# DigitalClock-7221.net
KiCad netlist of a schematic drawn in EAGLE
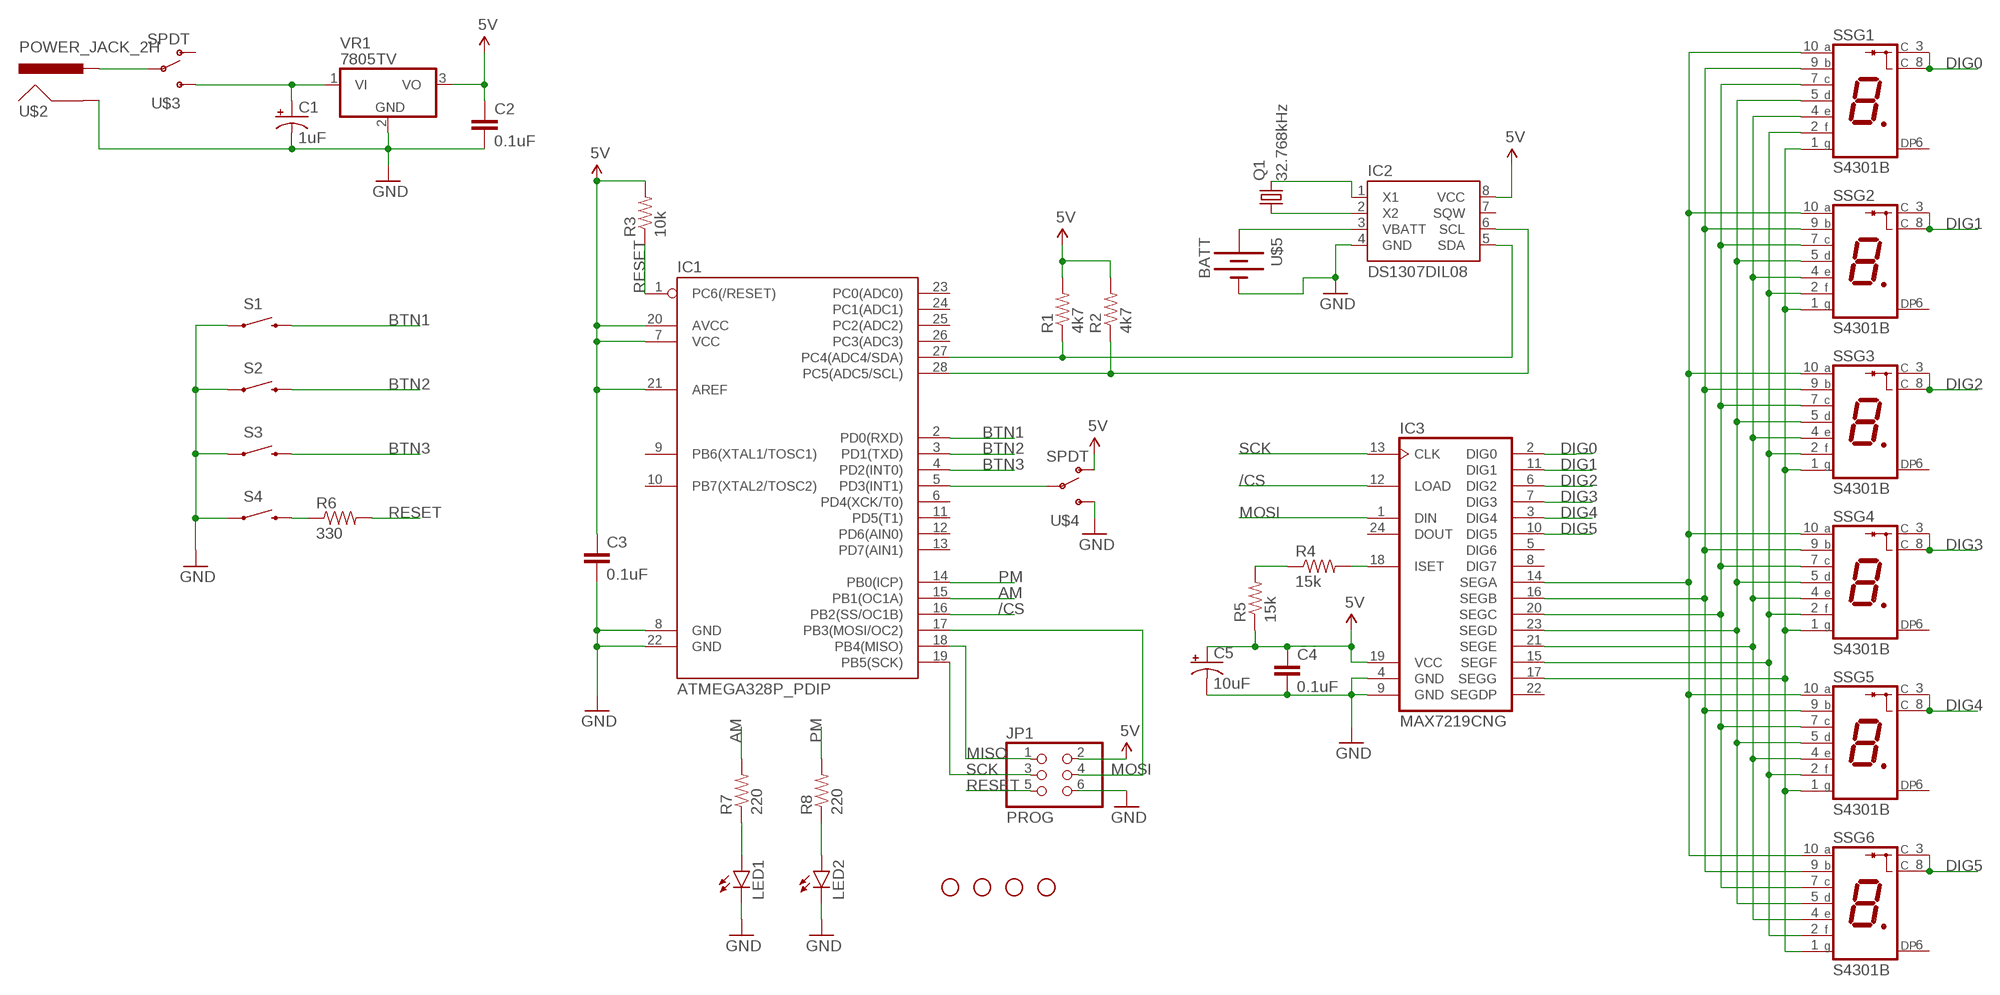
[diagram p0: schematic, sheet 1]

(export (version "E")
  (design (tool "Eeschema 10.0.6"))
  (components
    (comp (ref "C1")
      (value "1uF")
      (footprint "eagle-import:CPOL-RADIAL-10UF-25V")
      (libsource (lib "eagle-import") (part "CAP_POLPTH2"))
    )
    (comp (ref "C2")
      (value "0.1uF")
      (footprint "eagle-import:CAP-PTH-5MM")
      (libsource (lib "eagle-import") (part "CAPPTH1"))
    )
    (comp (ref "C3")
      (value "0.1uF")
      (footprint "eagle-import:CAP-PTH-5MM")
      (libsource (lib "eagle-import") (part "CAPPTH1"))
    )
    (comp (ref "C4")
      (value "0.1uF")
      (footprint "eagle-import:CAP-PTH-5MM")
      (libsource (lib "eagle-import") (part "CAPPTH1"))
    )
    (comp (ref "C5")
      (value "10uF")
      (footprint "eagle-import:CPOL-RADIAL-10UF-25V")
      (libsource (lib "eagle-import") (part "CAP_POLPTH2"))
    )
    (comp (ref "H1")
      (value "STAND-OFF")
      (footprint "eagle-import:STAND-OFF")
      (libsource (lib "eagle-import") (part "STAND-OFF"))
    )
    (comp (ref "H2")
      (value "STAND-OFF")
      (footprint "eagle-import:STAND-OFF")
      (libsource (lib "eagle-import") (part "STAND-OFF"))
    )
    (comp (ref "H3")
      (value "STAND-OFF")
      (footprint "eagle-import:STAND-OFF")
      (libsource (lib "eagle-import") (part "STAND-OFF"))
    )
    (comp (ref "H4")
      (value "STAND-OFF")
      (footprint "eagle-import:STAND-OFF")
      (libsource (lib "eagle-import") (part "STAND-OFF"))
    )
    (comp (ref "IC1")
      (value "ATMEGA328P_PDIP")
      (footprint "eagle-import:DIL28-3")
      (libsource (lib "eagle-import") (part "ATMEGA328P_PDIP"))
    )
    (comp (ref "IC2")
      (value "DS1307DIL08")
      (footprint "eagle-import:DIL08")
      (libsource (lib "eagle-import") (part "DS1307DIL08"))
    )
    (comp (ref "IC3")
      (value "MAX7219CNG")
      (footprint "eagle-import:DIL24-3")
      (fields (field (name "MF") "MAXIM"))
      (libsource (lib "eagle-import") (part "MAX7219CNG"))
    )
    (comp (ref "JP1")
      (value "PROG")
      (footprint "eagle-import:2X03")
      (libsource (lib "eagle-import") (part "PINHD-2X3"))
    )
    (comp (ref "LED1")
      (value "LED5MM")
      (footprint "eagle-import:LED5MM")
      (libsource (lib "eagle-import") (part "LED5MM"))
    )
    (comp (ref "LED2")
      (value "LED5MM")
      (footprint "eagle-import:LED5MM")
      (libsource (lib "eagle-import") (part "LED5MM"))
    )
    (comp (ref "Q1")
      (value "32.768kHz")
      (footprint "eagle-import:TC26V")
      (libsource (lib "eagle-import") (part "CRYSTALTC26V"))
    )
    (comp (ref "R1")
      (value "4k7")
      (footprint "eagle-import:AXIAL-0.3")
      (libsource (lib "eagle-import") (part "RESISTORAXIAL-0.3"))
    )
    (comp (ref "R2")
      (value "4k7")
      (footprint "eagle-import:AXIAL-0.3")
      (libsource (lib "eagle-import") (part "RESISTORAXIAL-0.3"))
    )
    (comp (ref "R3")
      (value "10k")
      (footprint "eagle-import:AXIAL-0.3")
      (libsource (lib "eagle-import") (part "RESISTORAXIAL-0.3"))
    )
    (comp (ref "R4")
      (value "15k")
      (footprint "eagle-import:AXIAL-0.3")
      (libsource (lib "eagle-import") (part "RESISTORAXIAL-0.3"))
    )
    (comp (ref "R5")
      (value "15k")
      (footprint "eagle-import:AXIAL-0.3")
      (libsource (lib "eagle-import") (part "RESISTORAXIAL-0.3"))
    )
    (comp (ref "R6")
      (value "330")
      (footprint "eagle-import:AXIAL-0.3")
      (libsource (lib "eagle-import") (part "RESISTORAXIAL-0.3"))
    )
    (comp (ref "R7")
      (value "220")
      (footprint "eagle-import:AXIAL-0.3")
      (libsource (lib "eagle-import") (part "RESISTORAXIAL-0.3"))
    )
    (comp (ref "R8")
      (value "220")
      (footprint "eagle-import:AXIAL-0.3")
      (libsource (lib "eagle-import") (part "RESISTORAXIAL-0.3"))
    )
    (comp (ref "S1")
      (value "SWITCH-MOMENTARY-2PTH")
      (footprint "eagle-import:TACTILE-PTH")
      (libsource (lib "eagle-import") (part "SWITCH-MOMENTARY-2PTH"))
    )
    (comp (ref "S2")
      (value "SWITCH-MOMENTARY-2PTH")
      (footprint "eagle-import:TACTILE-PTH")
      (libsource (lib "eagle-import") (part "SWITCH-MOMENTARY-2PTH"))
    )
    (comp (ref "S3")
      (value "SWITCH-MOMENTARY-2PTH")
      (footprint "eagle-import:TACTILE-PTH")
      (libsource (lib "eagle-import") (part "SWITCH-MOMENTARY-2PTH"))
    )
    (comp (ref "S4")
      (value "SWITCH-MOMENTARY-2PTH")
      (footprint "eagle-import:TACTILE-PTH")
      (libsource (lib "eagle-import") (part "SWITCH-MOMENTARY-2PTH"))
    )
    (comp (ref "SSG1")
      (value "S4301B")
      (footprint "eagle-import:S4301B")
      (libsource (lib "eagle-import") (part "S4301B"))
    )
    (comp (ref "SSG2")
      (value "S4301B")
      (footprint "eagle-import:S4301B")
      (libsource (lib "eagle-import") (part "S4301B"))
    )
    (comp (ref "SSG3")
      (value "S4301B")
      (footprint "eagle-import:S4301B")
      (libsource (lib "eagle-import") (part "S4301B"))
    )
    (comp (ref "SSG4")
      (value "S4301B")
      (footprint "eagle-import:S4301B")
      (libsource (lib "eagle-import") (part "S4301B"))
    )
    (comp (ref "SSG5")
      (value "S4301B")
      (footprint "eagle-import:S4301B")
      (libsource (lib "eagle-import") (part "S4301B"))
    )
    (comp (ref "SSG6")
      (value "S4301B")
      (footprint "eagle-import:S4301B")
      (libsource (lib "eagle-import") (part "S4301B"))
    )
    (comp (ref "U$2")
      (value "POWER_JACK_2H")
      (footprint "eagle-import:POWER_JACK_2H")
      (libsource (lib "eagle-import") (part "POWER_JACK_2H"))
    )
    (comp (ref "U$3")
      (value "SPDT")
      (footprint "eagle-import:SPDT")
      (libsource (lib "eagle-import") (part "SPDT"))
    )
    (comp (ref "U$4")
      (value "SPDT")
      (footprint "eagle-import:SPDT")
      (libsource (lib "eagle-import") (part "SPDT"))
    )
    (comp (ref "U$5")
      (value "BATT")
      (footprint "eagle-import:BATT")
      (libsource (lib "eagle-import") (part "BATT"))
    )
    (comp (ref "VR1")
      (value "7805TV")
      (footprint "eagle-import:TO220V")
      (libsource (lib "eagle-import") (part "78TV05"))
    )
  )
  (nets
    (net (code "1") (name "/AM") (class "Default")
      (node (ref "IC1") (pin "15") (pinfunction "PB1(OC1A)_15") (pintype "bidirectional"))
      (node (ref "R7") (pin "P$2") (pinfunction "2_P$2") (pintype "passive"))
    )
    (net (code "2") (name "/BTN1") (class "Default")
      (node (ref "IC1") (pin "2") (pinfunction "PD0(RXD)_2") (pintype "bidirectional"))
      (node (ref "S1") (pin "3") (pinfunction "2_3") (pintype "passive"))
    )
    (net (code "3") (name "/BTN2") (class "Default")
      (node (ref "IC1") (pin "3") (pinfunction "PD1(TXD)_3") (pintype "bidirectional"))
      (node (ref "S2") (pin "3") (pinfunction "2_3") (pintype "passive"))
    )
    (net (code "4") (name "/BTN3") (class "Default")
      (node (ref "IC1") (pin "4") (pinfunction "PD2(INT0)_4") (pintype "bidirectional"))
      (node (ref "S3") (pin "3") (pinfunction "2_3") (pintype "passive"))
    )
    (net (code "5") (name "/DIG0") (class "Default")
      (node (ref "IC3") (pin "2") (pinfunction "DIG0_2") (pintype "output"))
      (node (ref "SSG1") (pin "3") (pinfunction "C_3") (pintype "passive"))
      (node (ref "SSG1") (pin "8") (pinfunction "C_8") (pintype "passive"))
    )
    (net (code "6") (name "/DIG1") (class "Default")
      (node (ref "IC3") (pin "11") (pinfunction "DIG1_11") (pintype "output"))
      (node (ref "SSG2") (pin "3") (pinfunction "C_3") (pintype "passive"))
      (node (ref "SSG2") (pin "8") (pinfunction "C_8") (pintype "passive"))
    )
    (net (code "7") (name "/DIG2") (class "Default")
      (node (ref "IC3") (pin "6") (pinfunction "DIG2_6") (pintype "output"))
      (node (ref "SSG3") (pin "3") (pinfunction "C_3") (pintype "passive"))
      (node (ref "SSG3") (pin "8") (pinfunction "C_8") (pintype "passive"))
    )
    (net (code "8") (name "/DIG3") (class "Default")
      (node (ref "IC3") (pin "7") (pinfunction "DIG3_7") (pintype "output"))
      (node (ref "SSG4") (pin "3") (pinfunction "C_3") (pintype "passive"))
      (node (ref "SSG4") (pin "8") (pinfunction "C_8") (pintype "passive"))
    )
    (net (code "9") (name "/DIG4") (class "Default")
      (node (ref "IC3") (pin "3") (pinfunction "DIG4_3") (pintype "output"))
      (node (ref "SSG5") (pin "3") (pinfunction "C_3") (pintype "passive"))
      (node (ref "SSG5") (pin "8") (pinfunction "C_8") (pintype "passive"))
    )
    (net (code "10") (name "/DIG5") (class "Default")
      (node (ref "IC3") (pin "10") (pinfunction "DIG5_10") (pintype "output"))
      (node (ref "SSG6") (pin "3") (pinfunction "C_3") (pintype "passive"))
      (node (ref "SSG6") (pin "8") (pinfunction "C_8") (pintype "passive"))
    )
    (net (code "11") (name "/MISO") (class "Default")
      (node (ref "IC1") (pin "18") (pinfunction "PB4(MISO)_18") (pintype "bidirectional"))
      (node (ref "JP1") (pin "1") (pinfunction "1_1") (pintype "passive"))
    )
    (net (code "12") (name "/MOSI") (class "Default")
      (node (ref "IC1") (pin "17") (pinfunction "PB3(MOSI/OC2)_17") (pintype "bidirectional"))
      (node (ref "IC3") (pin "1") (pinfunction "DIN_1") (pintype "input"))
      (node (ref "JP1") (pin "4") (pinfunction "4_4") (pintype "passive"))
    )
    (net (code "13") (name "/PM") (class "Default")
      (node (ref "IC1") (pin "14") (pinfunction "PB0(ICP)_14") (pintype "bidirectional"))
      (node (ref "R8") (pin "P$2") (pinfunction "2_P$2") (pintype "passive"))
    )
    (net (code "14") (name "/RESET") (class "Default")
      (node (ref "IC1") (pin "1") (pinfunction "PC6(/RESET)_1") (pintype "bidirectional"))
      (node (ref "JP1") (pin "5") (pinfunction "5_5") (pintype "passive"))
      (node (ref "R3") (pin "P$1") (pinfunction "1_P$1") (pintype "passive"))
      (node (ref "R6") (pin "P$2") (pinfunction "2_P$2") (pintype "passive"))
    )
    (net (code "15") (name "/SCK") (class "Default")
      (node (ref "IC1") (pin "19") (pinfunction "PB5(SCK)_19") (pintype "bidirectional"))
      (node (ref "IC3") (pin "13") (pinfunction "CLK_13") (pintype "input"))
      (node (ref "JP1") (pin "3") (pinfunction "3_3") (pintype "passive"))
    )
    (net (code "16") (name "/{slash}CS") (class "Default")
      (node (ref "IC1") (pin "16") (pinfunction "PB2(SS/OC1B)_16") (pintype "bidirectional"))
      (node (ref "IC3") (pin "12") (pinfunction "LOAD_12") (pintype "input"))
    )
    (net (code "17") (name "5V") (class "Default")
      (node (ref "C2") (pin "1") (pinfunction "1_1") (pintype "passive"))
      (node (ref "C3") (pin "1") (pinfunction "1_1") (pintype "passive"))
      (node (ref "C4") (pin "1") (pinfunction "1_1") (pintype "passive"))
      (node (ref "C5") (pin "1") (pinfunction "+_1") (pintype "passive"))
      (node (ref "IC1") (pin "20") (pinfunction "AVCC_20") (pintype "bidirectional"))
      (node (ref "IC1") (pin "21") (pinfunction "AREF_21") (pintype "bidirectional"))
      (node (ref "IC1") (pin "7") (pinfunction "VCC_7") (pintype "bidirectional"))
      (node (ref "IC2") (pin "8") (pinfunction "VCC_8") (pintype "bidirectional"))
      (node (ref "IC3") (pin "19") (pinfunction "VCC_19") (pintype "power_in"))
      (node (ref "JP1") (pin "2") (pinfunction "2_2") (pintype "passive"))
      (node (ref "R1") (pin "P$2") (pinfunction "2_P$2") (pintype "passive"))
      (node (ref "R2") (pin "P$2") (pinfunction "2_P$2") (pintype "passive"))
      (node (ref "R3") (pin "P$2") (pinfunction "2_P$2") (pintype "passive"))
      (node (ref "R5") (pin "P$1") (pinfunction "1_P$1") (pintype "passive"))
      (node (ref "U$4") (pin "P$2") (pinfunction "O_P$2") (pintype "passive"))
      (node (ref "VR1") (pin "3") (pinfunction "VO_3") (pintype "passive"))
    )
    (net (code "18") (name "GND") (class "Default")
      (node (ref "C1") (pin "2") (pinfunction "-_2") (pintype "passive"))
      (node (ref "C2") (pin "2") (pinfunction "2_2") (pintype "passive"))
      (node (ref "C3") (pin "2") (pinfunction "2_2") (pintype "passive"))
      (node (ref "C4") (pin "2") (pinfunction "2_2") (pintype "passive"))
      (node (ref "C5") (pin "2") (pinfunction "-_2") (pintype "passive"))
      (node (ref "IC1") (pin "22") (pinfunction "GND_22") (pintype "bidirectional"))
      (node (ref "IC1") (pin "8") (pinfunction "GND_8") (pintype "bidirectional"))
      (node (ref "IC2") (pin "4") (pinfunction "GND_4") (pintype "bidirectional"))
      (node (ref "IC3") (pin "4") (pinfunction "GND_4") (pintype "power_in"))
      (node (ref "IC3") (pin "9") (pinfunction "GND_9") (pintype "power_in"))
      (node (ref "JP1") (pin "6") (pinfunction "6_6") (pintype "passive"))
      (node (ref "LED1") (pin "K") (pinfunction "C_K") (pintype "passive"))
      (node (ref "LED2") (pin "K") (pinfunction "C_K") (pintype "passive"))
      (node (ref "S1") (pin "1") (pinfunction "1_1") (pintype "passive"))
      (node (ref "S2") (pin "1") (pinfunction "1_1") (pintype "passive"))
      (node (ref "S3") (pin "1") (pinfunction "1_1") (pintype "passive"))
      (node (ref "S4") (pin "1") (pinfunction "1_1") (pintype "passive"))
      (node (ref "U$2") (pin "P$1") (pinfunction "GND_P$1") (pintype "bidirectional"))
      (node (ref "U$4") (pin "P$3") (pinfunction "S_P$3") (pintype "passive"))
      (node (ref "U$5") (pin "P$2") (pinfunction "-_P$2") (pintype "power_in"))
      (node (ref "VR1") (pin "2") (pinfunction "GND_2") (pintype "passive"))
    )
    (net (code "19") (name "Net-(C1-+)") (class "Default")
      (node (ref "C1") (pin "1") (pinfunction "+_1") (pintype "passive"))
      (node (ref "U$3") (pin "P$3") (pinfunction "S_P$3") (pintype "passive"))
      (node (ref "VR1") (pin "1") (pinfunction "VI_1") (pintype "input"))
    )
    (net (code "20") (name "Net-(IC1-PC4(ADC4{slash}SDA))") (class "Default")
      (node (ref "IC1") (pin "27") (pinfunction "PC4(ADC4/SDA)_27") (pintype "bidirectional"))
      (node (ref "IC2") (pin "5") (pinfunction "SDA_5") (pintype "bidirectional"))
      (node (ref "R1") (pin "P$1") (pinfunction "1_P$1") (pintype "passive"))
    )
    (net (code "21") (name "Net-(IC1-PC5(ADC5{slash}SCL))") (class "Default")
      (node (ref "IC1") (pin "28") (pinfunction "PC5(ADC5/SCL)_28") (pintype "bidirectional"))
      (node (ref "IC2") (pin "6") (pinfunction "SCL_6") (pintype "bidirectional"))
      (node (ref "R2") (pin "P$1") (pinfunction "1_P$1") (pintype "passive"))
    )
    (net (code "22") (name "Net-(IC1-PD3(INT1))") (class "Default")
      (node (ref "IC1") (pin "5") (pinfunction "PD3(INT1)_5") (pintype "bidirectional"))
      (node (ref "U$4") (pin "P$1") (pinfunction "P_P$1") (pintype "passive"))
    )
    (net (code "23") (name "Net-(IC2-VBATT)") (class "Default")
      (node (ref "IC2") (pin "3") (pinfunction "VBATT_3") (pintype "bidirectional"))
      (node (ref "U$5") (pin "P$1") (pinfunction "+_P$1") (pintype "power_in"))
    )
    (net (code "24") (name "Net-(IC2-X1)") (class "Default")
      (node (ref "IC2") (pin "1") (pinfunction "X1_1") (pintype "bidirectional"))
      (node (ref "Q1") (pin "2") (pinfunction "2_2") (pintype "passive"))
    )
    (net (code "25") (name "Net-(IC2-X2)") (class "Default")
      (node (ref "IC2") (pin "2") (pinfunction "X2_2") (pintype "bidirectional"))
      (node (ref "Q1") (pin "1") (pinfunction "1_1") (pintype "passive"))
    )
    (net (code "26") (name "Net-(IC3-ISET)") (class "Default")
      (node (ref "IC3") (pin "18") (pinfunction "ISET_18") (pintype "input"))
      (node (ref "R4") (pin "P$2") (pinfunction "2_P$2") (pintype "passive"))
    )
    (net (code "27") (name "Net-(IC3-SEGA)") (class "Default")
      (node (ref "IC3") (pin "14") (pinfunction "SEGA_14") (pintype "output"))
      (node (ref "SSG1") (pin "10") (pinfunction "A_10") (pintype "passive"))
      (node (ref "SSG2") (pin "10") (pinfunction "A_10") (pintype "passive"))
      (node (ref "SSG3") (pin "10") (pinfunction "A_10") (pintype "passive"))
      (node (ref "SSG4") (pin "10") (pinfunction "A_10") (pintype "passive"))
      (node (ref "SSG5") (pin "10") (pinfunction "A_10") (pintype "passive"))
      (node (ref "SSG6") (pin "10") (pinfunction "A_10") (pintype "passive"))
    )
    (net (code "28") (name "Net-(IC3-SEGB)") (class "Default")
      (node (ref "IC3") (pin "16") (pinfunction "SEGB_16") (pintype "output"))
      (node (ref "SSG1") (pin "9") (pinfunction "B_9") (pintype "passive"))
      (node (ref "SSG2") (pin "9") (pinfunction "B_9") (pintype "passive"))
      (node (ref "SSG3") (pin "9") (pinfunction "B_9") (pintype "passive"))
      (node (ref "SSG4") (pin "9") (pinfunction "B_9") (pintype "passive"))
      (node (ref "SSG5") (pin "9") (pinfunction "B_9") (pintype "passive"))
      (node (ref "SSG6") (pin "9") (pinfunction "B_9") (pintype "passive"))
    )
    (net (code "29") (name "Net-(IC3-SEGC)") (class "Default")
      (node (ref "IC3") (pin "20") (pinfunction "SEGC_20") (pintype "output"))
      (node (ref "SSG1") (pin "7") (pinfunction "C_7") (pintype "passive"))
      (node (ref "SSG2") (pin "7") (pinfunction "C_7") (pintype "passive"))
      (node (ref "SSG3") (pin "7") (pinfunction "C_7") (pintype "passive"))
      (node (ref "SSG4") (pin "7") (pinfunction "C_7") (pintype "passive"))
      (node (ref "SSG5") (pin "7") (pinfunction "C_7") (pintype "passive"))
      (node (ref "SSG6") (pin "7") (pinfunction "C_7") (pintype "passive"))
    )
    (net (code "30") (name "Net-(IC3-SEGD)") (class "Default")
      (node (ref "IC3") (pin "23") (pinfunction "SEGD_23") (pintype "output"))
      (node (ref "SSG1") (pin "5") (pinfunction "D_5") (pintype "passive"))
      (node (ref "SSG2") (pin "5") (pinfunction "D_5") (pintype "passive"))
      (node (ref "SSG3") (pin "5") (pinfunction "D_5") (pintype "passive"))
      (node (ref "SSG4") (pin "5") (pinfunction "D_5") (pintype "passive"))
      (node (ref "SSG5") (pin "5") (pinfunction "D_5") (pintype "passive"))
      (node (ref "SSG6") (pin "5") (pinfunction "D_5") (pintype "passive"))
    )
    (net (code "31") (name "Net-(IC3-SEGE)") (class "Default")
      (node (ref "IC3") (pin "21") (pinfunction "SEGE_21") (pintype "output"))
      (node (ref "SSG1") (pin "4") (pinfunction "E_4") (pintype "passive"))
      (node (ref "SSG2") (pin "4") (pinfunction "E_4") (pintype "passive"))
      (node (ref "SSG3") (pin "4") (pinfunction "E_4") (pintype "passive"))
      (node (ref "SSG4") (pin "4") (pinfunction "E_4") (pintype "passive"))
      (node (ref "SSG5") (pin "4") (pinfunction "E_4") (pintype "passive"))
      (node (ref "SSG6") (pin "4") (pinfunction "E_4") (pintype "passive"))
    )
    (net (code "32") (name "Net-(IC3-SEGF)") (class "Default")
      (node (ref "IC3") (pin "15") (pinfunction "SEGF_15") (pintype "output"))
      (node (ref "SSG1") (pin "2") (pinfunction "F_2") (pintype "passive"))
      (node (ref "SSG2") (pin "2") (pinfunction "F_2") (pintype "passive"))
      (node (ref "SSG3") (pin "2") (pinfunction "F_2") (pintype "passive"))
      (node (ref "SSG4") (pin "2") (pinfunction "F_2") (pintype "passive"))
      (node (ref "SSG5") (pin "2") (pinfunction "F_2") (pintype "passive"))
      (node (ref "SSG6") (pin "2") (pinfunction "F_2") (pintype "passive"))
    )
    (net (code "33") (name "Net-(IC3-SEGG)") (class "Default")
      (node (ref "IC3") (pin "17") (pinfunction "SEGG_17") (pintype "output"))
      (node (ref "SSG1") (pin "1") (pinfunction "G_1") (pintype "passive"))
      (node (ref "SSG2") (pin "1") (pinfunction "G_1") (pintype "passive"))
      (node (ref "SSG3") (pin "1") (pinfunction "G_1") (pintype "passive"))
      (node (ref "SSG4") (pin "1") (pinfunction "G_1") (pintype "passive"))
      (node (ref "SSG5") (pin "1") (pinfunction "G_1") (pintype "passive"))
      (node (ref "SSG6") (pin "1") (pinfunction "G_1") (pintype "passive"))
    )
    (net (code "34") (name "Net-(R4-1)") (class "Default")
      (node (ref "R4") (pin "P$1") (pinfunction "1_P$1") (pintype "passive"))
      (node (ref "R5") (pin "P$2") (pinfunction "2_P$2") (pintype "passive"))
    )
    (net (code "35") (name "Net-(R6-1)") (class "Default")
      (node (ref "R6") (pin "P$1") (pinfunction "1_P$1") (pintype "passive"))
      (node (ref "S4") (pin "3") (pinfunction "2_3") (pintype "passive"))
    )
    (net (code "36") (name "Net-(R7-1)") (class "Default")
      (node (ref "LED1") (pin "A") (pinfunction "A_A") (pintype "passive"))
      (node (ref "R7") (pin "P$1") (pinfunction "1_P$1") (pintype "passive"))
    )
    (net (code "37") (name "Net-(R8-1)") (class "Default")
      (node (ref "LED2") (pin "A") (pinfunction "A_A") (pintype "passive"))
      (node (ref "R8") (pin "P$1") (pinfunction "1_P$1") (pintype "passive"))
    )
    (net (code "38") (name "Net-(U$2-PWR)") (class "Default")
      (node (ref "U$2") (pin "P$2") (pinfunction "PWR_P$2") (pintype "bidirectional"))
      (node (ref "U$3") (pin "P$1") (pinfunction "P_P$1") (pintype "passive"))
    )
    (net (code "39") (name "unconnected-(IC1-PB6(XTAL1{slash}TOSC1)-Pad9)") (class "Default")
      (node (ref "IC1") (pin "9") (pinfunction "PB6(XTAL1/TOSC1)_9") (pintype "bidirectional"))
    )
    (net (code "40") (name "unconnected-(IC1-PB7(XTAL2{slash}TOSC2)-Pad10)") (class "Default")
      (node (ref "IC1") (pin "10") (pinfunction "PB7(XTAL2/TOSC2)_10") (pintype "bidirectional"))
    )
    (net (code "41") (name "unconnected-(IC1-PC0(ADC0)-Pad23)") (class "Default")
      (node (ref "IC1") (pin "23") (pinfunction "PC0(ADC0)_23") (pintype "bidirectional"))
    )
    (net (code "42") (name "unconnected-(IC1-PC1(ADC1)-Pad24)") (class "Default")
      (node (ref "IC1") (pin "24") (pinfunction "PC1(ADC1)_24") (pintype "bidirectional"))
    )
    (net (code "43") (name "unconnected-(IC1-PC2(ADC2)-Pad25)") (class "Default")
      (node (ref "IC1") (pin "25") (pinfunction "PC2(ADC2)_25") (pintype "bidirectional"))
    )
    (net (code "44") (name "unconnected-(IC1-PC3(ADC3)-Pad26)") (class "Default")
      (node (ref "IC1") (pin "26") (pinfunction "PC3(ADC3)_26") (pintype "bidirectional"))
    )
    (net (code "45") (name "unconnected-(IC1-PD4(XCK{slash}T0)-Pad6)") (class "Default")
      (node (ref "IC1") (pin "6") (pinfunction "PD4(XCK/T0)_6") (pintype "bidirectional"))
    )
    (net (code "46") (name "unconnected-(IC1-PD5(T1)-Pad11)") (class "Default")
      (node (ref "IC1") (pin "11") (pinfunction "PD5(T1)_11") (pintype "bidirectional"))
    )
    (net (code "47") (name "unconnected-(IC1-PD6(AIN0)-Pad12)") (class "Default")
      (node (ref "IC1") (pin "12") (pinfunction "PD6(AIN0)_12") (pintype "bidirectional"))
    )
    (net (code "48") (name "unconnected-(IC1-PD7(AIN1)-Pad13)") (class "Default")
      (node (ref "IC1") (pin "13") (pinfunction "PD7(AIN1)_13") (pintype "bidirectional"))
    )
    (net (code "49") (name "unconnected-(IC2-SQW-Pad7)") (class "Default")
      (node (ref "IC2") (pin "7") (pinfunction "SQW_7") (pintype "bidirectional"))
    )
    (net (code "50") (name "unconnected-(IC3-DIG6-Pad5)") (class "Default")
      (node (ref "IC3") (pin "5") (pinfunction "DIG6_5") (pintype "output"))
    )
    (net (code "51") (name "unconnected-(IC3-DIG7-Pad8)") (class "Default")
      (node (ref "IC3") (pin "8") (pinfunction "DIG7_8") (pintype "output"))
    )
    (net (code "52") (name "unconnected-(IC3-DOUT-Pad24)") (class "Default")
      (node (ref "IC3") (pin "24") (pinfunction "DOUT_24") (pintype "output"))
    )
    (net (code "53") (name "unconnected-(IC3-SEGDP-Pad22)") (class "Default")
      (node (ref "IC3") (pin "22") (pinfunction "SEGDP_22") (pintype "output"))
    )
    (net (code "54") (name "unconnected-(SSG1-DP-Pad6)") (class "Default")
      (node (ref "SSG1") (pin "6") (pinfunction "DP_6") (pintype "passive"))
    )
    (net (code "55") (name "unconnected-(SSG2-DP-Pad6)") (class "Default")
      (node (ref "SSG2") (pin "6") (pinfunction "DP_6") (pintype "passive"))
    )
    (net (code "56") (name "unconnected-(SSG3-DP-Pad6)") (class "Default")
      (node (ref "SSG3") (pin "6") (pinfunction "DP_6") (pintype "passive"))
    )
    (net (code "57") (name "unconnected-(SSG4-DP-Pad6)") (class "Default")
      (node (ref "SSG4") (pin "6") (pinfunction "DP_6") (pintype "passive"))
    )
    (net (code "58") (name "unconnected-(SSG5-DP-Pad6)") (class "Default")
      (node (ref "SSG5") (pin "6") (pinfunction "DP_6") (pintype "passive"))
    )
    (net (code "59") (name "unconnected-(SSG6-DP-Pad6)") (class "Default")
      (node (ref "SSG6") (pin "6") (pinfunction "DP_6") (pintype "passive"))
    )
    (net (code "60") (name "unconnected-(U$3-O-PadP$2)") (class "Default")
      (node (ref "U$3") (pin "P$2") (pinfunction "O_P$2") (pintype "passive"))
    )
  )
)
